# dlphat.net
KiCad netlist of a schematic drawn in EAGLE
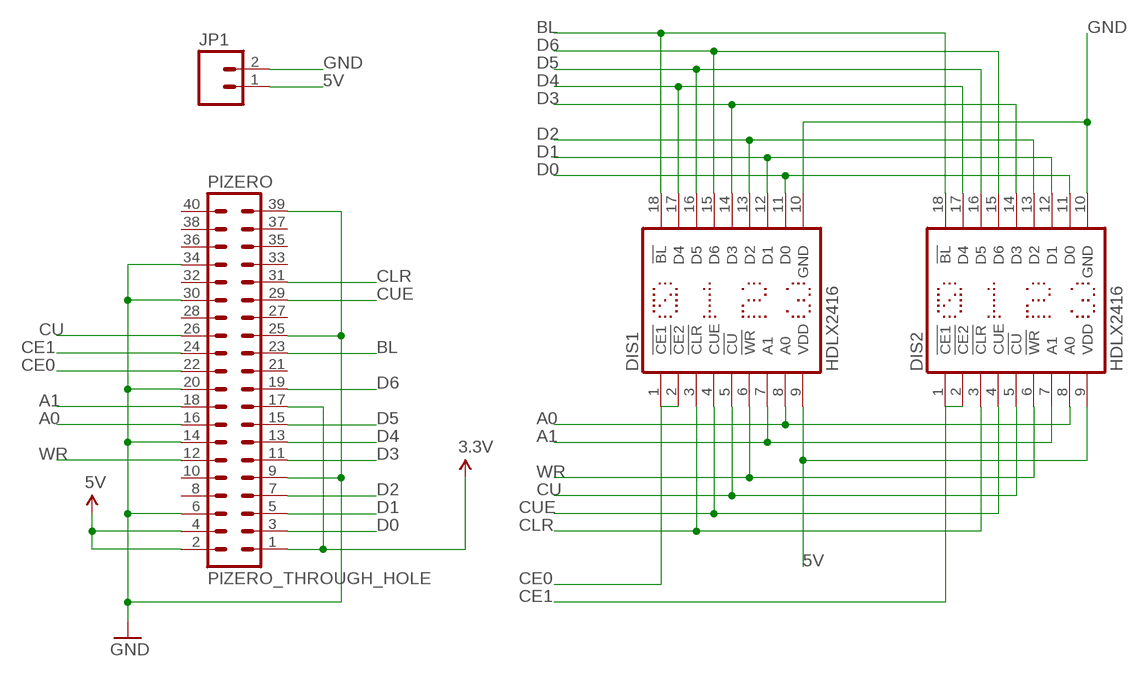
[diagram p0: schematic, sheet 1]

(export (version "E")
  (design (tool "Eeschema 10.0.6"))
  (components
    (comp (ref "DIS1")
      (value "HDLX2416")
      (footprint "eagle-import:HDLX2416")
      (libsource (lib "eagle-import") (part "HDLX2416"))
    )
    (comp (ref "DIS2")
      (value "HDLX2416")
      (footprint "eagle-import:HDLX2416")
      (libsource (lib "eagle-import") (part "HDLX2416"))
    )
    (comp (ref "JP1")
      (value "M02POLAR")
      (footprint "eagle-import:MOLEX-1X2")
      (libsource (lib "eagle-import") (part "M02POLAR"))
    )
    (comp (ref "PIZERO")
      (value "PIZERO_THROUGH_HOLE")
      (footprint "eagle-import:PIZERO_THOUGH_HOLE")
      (libsource (lib "eagle-import") (part "PIZERO_THROUGH_HOLE"))
    )
  )
  (nets
    (net (code "1") (name "/A0") (class "Default")
      (node (ref "DIS1") (pin "8") (pinfunction "A0_8") (pintype "input"))
      (node (ref "DIS2") (pin "8") (pinfunction "A0_8") (pintype "input"))
      (node (ref "PIZERO") (pin "16") (pinfunction "16_16") (pintype "passive"))
    )
    (net (code "2") (name "/A1") (class "Default")
      (node (ref "DIS1") (pin "7") (pinfunction "A1_7") (pintype "input"))
      (node (ref "DIS2") (pin "7") (pinfunction "A1_7") (pintype "input"))
      (node (ref "PIZERO") (pin "18") (pinfunction "18_18") (pintype "passive"))
    )
    (net (code "3") (name "/BL") (class "Default")
      (node (ref "DIS1") (pin "18") (pinfunction "~{BL}_18") (pintype "input"))
      (node (ref "DIS2") (pin "18") (pinfunction "~{BL}_18") (pintype "input"))
      (node (ref "PIZERO") (pin "23") (pinfunction "23_23") (pintype "passive"))
    )
    (net (code "4") (name "/CE0") (class "Default")
      (node (ref "DIS1") (pin "1") (pinfunction "~{CE1}_1") (pintype "input"))
      (node (ref "DIS1") (pin "2") (pinfunction "~{CE2}_2") (pintype "input"))
      (node (ref "PIZERO") (pin "22") (pinfunction "22_22") (pintype "passive"))
    )
    (net (code "5") (name "/CE1") (class "Default")
      (node (ref "DIS2") (pin "1") (pinfunction "~{CE1}_1") (pintype "input"))
      (node (ref "DIS2") (pin "2") (pinfunction "~{CE2}_2") (pintype "input"))
      (node (ref "PIZERO") (pin "24") (pinfunction "24_24") (pintype "passive"))
    )
    (net (code "6") (name "/CLR") (class "Default")
      (node (ref "DIS1") (pin "3") (pinfunction "~{CLR}_3") (pintype "input"))
      (node (ref "DIS2") (pin "3") (pinfunction "~{CLR}_3") (pintype "input"))
      (node (ref "PIZERO") (pin "31") (pinfunction "31_31") (pintype "passive"))
    )
    (net (code "7") (name "/CU") (class "Default")
      (node (ref "DIS1") (pin "5") (pinfunction "~{CU}_5") (pintype "input"))
      (node (ref "DIS2") (pin "5") (pinfunction "~{CU}_5") (pintype "input"))
      (node (ref "PIZERO") (pin "26") (pinfunction "26_26") (pintype "passive"))
    )
    (net (code "8") (name "/CUE") (class "Default")
      (node (ref "DIS1") (pin "4") (pinfunction "CUE_4") (pintype "input"))
      (node (ref "DIS2") (pin "4") (pinfunction "CUE_4") (pintype "input"))
      (node (ref "PIZERO") (pin "29") (pinfunction "29_29") (pintype "passive"))
    )
    (net (code "9") (name "/D0") (class "Default")
      (node (ref "DIS1") (pin "11") (pinfunction "D0_11") (pintype "input"))
      (node (ref "DIS2") (pin "11") (pinfunction "D0_11") (pintype "input"))
      (node (ref "PIZERO") (pin "3") (pinfunction "3_3") (pintype "passive"))
    )
    (net (code "10") (name "/D1") (class "Default")
      (node (ref "DIS1") (pin "12") (pinfunction "D1_12") (pintype "input"))
      (node (ref "DIS2") (pin "12") (pinfunction "D1_12") (pintype "input"))
      (node (ref "PIZERO") (pin "5") (pinfunction "5_5") (pintype "passive"))
    )
    (net (code "11") (name "/D2") (class "Default")
      (node (ref "DIS1") (pin "13") (pinfunction "D2_13") (pintype "input"))
      (node (ref "DIS2") (pin "13") (pinfunction "D2_13") (pintype "input"))
      (node (ref "PIZERO") (pin "7") (pinfunction "7_7") (pintype "passive"))
    )
    (net (code "12") (name "/D3") (class "Default")
      (node (ref "DIS1") (pin "14") (pinfunction "D3_14") (pintype "input"))
      (node (ref "DIS2") (pin "14") (pinfunction "D3_14") (pintype "input"))
      (node (ref "PIZERO") (pin "11") (pinfunction "11_11") (pintype "passive"))
    )
    (net (code "13") (name "/D4") (class "Default")
      (node (ref "DIS1") (pin "17") (pinfunction "D4_17") (pintype "input"))
      (node (ref "DIS2") (pin "17") (pinfunction "D4_17") (pintype "input"))
      (node (ref "PIZERO") (pin "13") (pinfunction "13_13") (pintype "passive"))
    )
    (net (code "14") (name "/D5") (class "Default")
      (node (ref "DIS1") (pin "16") (pinfunction "D5_16") (pintype "input"))
      (node (ref "DIS2") (pin "16") (pinfunction "D5_16") (pintype "input"))
      (node (ref "PIZERO") (pin "15") (pinfunction "15_15") (pintype "passive"))
    )
    (net (code "15") (name "/D6") (class "Default")
      (node (ref "DIS1") (pin "15") (pinfunction "D6_15") (pintype "input"))
      (node (ref "DIS2") (pin "15") (pinfunction "D6_15") (pintype "input"))
      (node (ref "PIZERO") (pin "19") (pinfunction "19_19") (pintype "passive"))
    )
    (net (code "16") (name "/WR") (class "Default")
      (node (ref "DIS1") (pin "6") (pinfunction "~{WR}_6") (pintype "input"))
      (node (ref "DIS2") (pin "6") (pinfunction "~{WR}_6") (pintype "input"))
      (node (ref "PIZERO") (pin "12") (pinfunction "12_12") (pintype "passive"))
    )
    (net (code "17") (name "3.3V") (class "Default")
      (node (ref "PIZERO") (pin "1") (pinfunction "1_1") (pintype "passive"))
      (node (ref "PIZERO") (pin "17") (pinfunction "17_17") (pintype "passive"))
    )
    (net (code "18") (name "5V") (class "Default")
      (node (ref "DIS1") (pin "9") (pinfunction "VDD_9") (pintype "power_in"))
      (node (ref "DIS2") (pin "9") (pinfunction "VDD_9") (pintype "power_in"))
      (node (ref "JP1") (pin "1") (pinfunction "1_1") (pintype "passive"))
      (node (ref "PIZERO") (pin "2") (pinfunction "2_2") (pintype "passive"))
      (node (ref "PIZERO") (pin "4") (pinfunction "4_4") (pintype "passive"))
    )
    (net (code "19") (name "GND") (class "Default")
      (node (ref "DIS1") (pin "10") (pinfunction "GND_10") (pintype "power_in"))
      (node (ref "DIS2") (pin "10") (pinfunction "GND_10") (pintype "power_in"))
      (node (ref "JP1") (pin "2") (pinfunction "2_2") (pintype "passive"))
      (node (ref "PIZERO") (pin "14") (pinfunction "14_14") (pintype "passive"))
      (node (ref "PIZERO") (pin "20") (pinfunction "20_20") (pintype "passive"))
      (node (ref "PIZERO") (pin "25") (pinfunction "25_25") (pintype "passive"))
      (node (ref "PIZERO") (pin "30") (pinfunction "30_30") (pintype "passive"))
      (node (ref "PIZERO") (pin "34") (pinfunction "34_34") (pintype "passive"))
      (node (ref "PIZERO") (pin "39") (pinfunction "39_39") (pintype "passive"))
      (node (ref "PIZERO") (pin "6") (pinfunction "6_6") (pintype "passive"))
      (node (ref "PIZERO") (pin "9") (pinfunction "9_9") (pintype "passive"))
    )
    (net (code "20") (name "unconnected-(PIZERO-Pad8)") (class "Default")
      (node (ref "PIZERO") (pin "8") (pinfunction "8_8") (pintype "passive"))
    )
    (net (code "21") (name "unconnected-(PIZERO-Pad10)") (class "Default")
      (node (ref "PIZERO") (pin "10") (pinfunction "10_10") (pintype "passive"))
    )
    (net (code "22") (name "unconnected-(PIZERO-Pad21)") (class "Default")
      (node (ref "PIZERO") (pin "21") (pinfunction "21_21") (pintype "passive"))
    )
    (net (code "23") (name "unconnected-(PIZERO-Pad27)") (class "Default")
      (node (ref "PIZERO") (pin "27") (pinfunction "27_27") (pintype "passive"))
    )
    (net (code "24") (name "unconnected-(PIZERO-Pad28)") (class "Default")
      (node (ref "PIZERO") (pin "28") (pinfunction "28_28") (pintype "passive"))
    )
    (net (code "25") (name "unconnected-(PIZERO-Pad32)") (class "Default")
      (node (ref "PIZERO") (pin "32") (pinfunction "32_32") (pintype "passive"))
    )
    (net (code "26") (name "unconnected-(PIZERO-Pad33)") (class "Default")
      (node (ref "PIZERO") (pin "33") (pinfunction "33_33") (pintype "passive"))
    )
    (net (code "27") (name "unconnected-(PIZERO-Pad35)") (class "Default")
      (node (ref "PIZERO") (pin "35") (pinfunction "35_35") (pintype "passive"))
    )
    (net (code "28") (name "unconnected-(PIZERO-Pad36)") (class "Default")
      (node (ref "PIZERO") (pin "36") (pinfunction "36_36") (pintype "passive"))
    )
    (net (code "29") (name "unconnected-(PIZERO-Pad37)") (class "Default")
      (node (ref "PIZERO") (pin "37") (pinfunction "37_37") (pintype "passive"))
    )
    (net (code "30") (name "unconnected-(PIZERO-Pad38)") (class "Default")
      (node (ref "PIZERO") (pin "38") (pinfunction "38_38") (pintype "passive"))
    )
    (net (code "31") (name "unconnected-(PIZERO-Pad40)") (class "Default")
      (node (ref "PIZERO") (pin "40") (pinfunction "40_40") (pintype "passive"))
    )
  )
)
